# 02_MSP430.net
KiCad netlist of a schematic drawn in Altium Designer
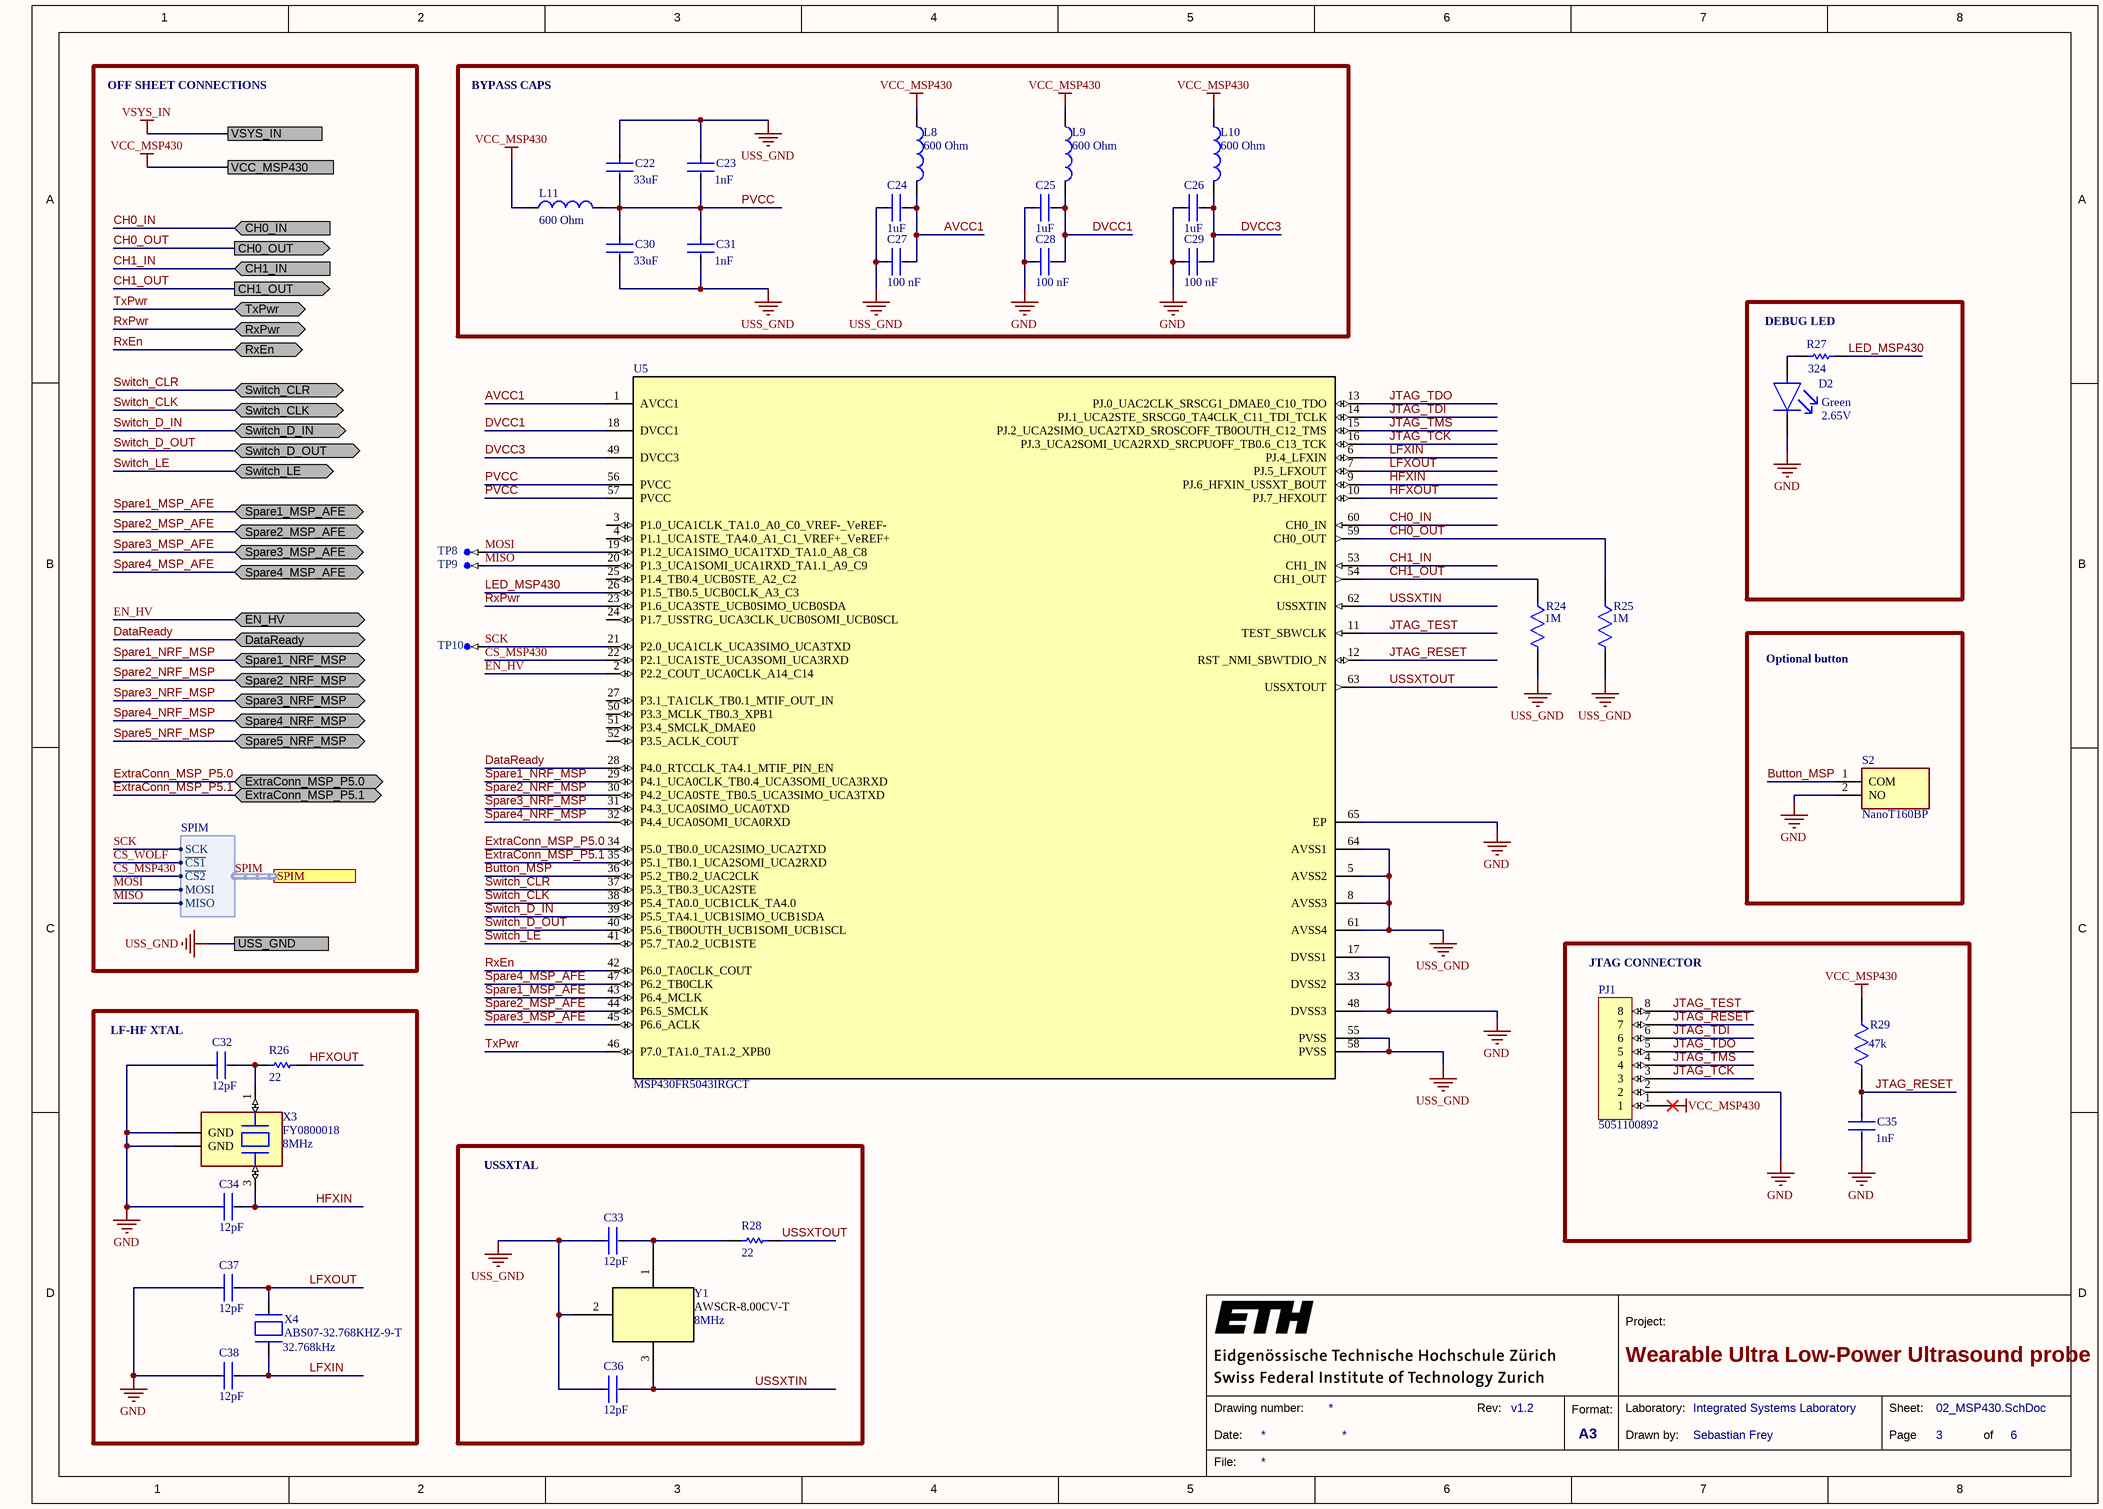
[diagram p0: 02_MSP430.SchDoc]

(export (version "E")
  (design (tool "Eeschema 10.0.6"))
  (components
    (comp (ref "C22")
      (value "C2012X5R1A336M125AC")
      (footprint "FP-C2012-125-0_2-IPC_A")
      (description "Multilayer Ceramic Capacitors 33μF ±20% 10V X5R SMD 0805")
      (fields (field (name "TOLERANCE") "20%") (field (name "CAPACITANCE") "33uF"))
      (libsource (lib "Altium Content Vault") (part "b4654b650e69147ec39a6b967a45e02"))
    )
    (comp (ref "C23")
      (value "GRM1555C1H102JA01D")
      (footprint "FP-GRM155-0_05-IPC_B")
      (description "Chip Multilayer Ceramic Capacitors for General Purpose, 0402, 1000pF, C0G, 30ppm/°C, 5%, 50V")
      (fields
        (field (name "TOLERANCE") "5%")
        (field (name "VOLTAGE") "50V")
        (field (name "CAPACITANCE") "1nF")
      )
      (libsource (lib "Altium Content Vault") (part "02cd4be3c70576c341d710602a673aa"))
    )
    (comp (ref "C24")
      (value "C1608X7R1C105K080AC")
      (footprint "FP-C1608-080-0_1-IPC_B")
      (description "Multilayer Ceramic Capacitors 1μF ±10% 16V X7R SMD 0603")
      (fields
        (field (name "VOLTAGE") "16V")
        (field (name "CAPACITANCE") "1uF")
        (field (name "TOLERANCE") "10%")
      )
      (libsource (lib "Altium Content Vault") (part "236180d848d6139a670b325ea6854c9"))
    )
    (comp (ref "C25")
      (value "C1608X7R1C105K080AC")
      (footprint "FP-C1608-080-0_1-IPC_B")
      (description "Multilayer Ceramic Capacitors 1μF ±10% 16V X7R SMD 0603")
      (fields
        (field (name "VOLTAGE") "16V")
        (field (name "CAPACITANCE") "1uF")
        (field (name "TOLERANCE") "10%")
      )
      (libsource (lib "Altium Content Vault") (part "236180d848d6139a670b325ea6854c9"))
    )
    (comp (ref "C26")
      (value "C1608X7R1C105K080AC")
      (footprint "FP-C1608-080-0_1-IPC_B")
      (description "Multilayer Ceramic Capacitors 1μF ±10% 16V X7R SMD 0603")
      (fields
        (field (name "VOLTAGE") "16V")
        (field (name "CAPACITANCE") "1uF")
        (field (name "TOLERANCE") "10%")
      )
      (libsource (lib "Altium Content Vault") (part "236180d848d6139a670b325ea6854c9"))
    )
    (comp (ref "C27")
      (value "100 nF")
      (footprint "FP-CC0402-MFG")
      (description "CAP CER 0.1UF 16V X7R 0402")
      (fields (field (name "MANUFACTURER") "YAGEO") (field (name "TOLERANCE") "0.1"))
      (libsource (lib "Altium Content Vault") (part "11868f565c42a9108669ba33697ecf6"))
    )
    (comp (ref "C28")
      (value "100 nF")
      (footprint "FP-CC0402-MFG")
      (description "CAP CER 0.1UF 16V X7R 0402")
      (fields (field (name "MANUFACTURER") "YAGEO") (field (name "TOLERANCE") "0.1"))
      (libsource (lib "Altium Content Vault") (part "11868f565c42a9108669ba33697ecf6"))
    )
    (comp (ref "C29")
      (value "100 nF")
      (footprint "FP-CC0402-MFG")
      (description "CAP CER 0.1UF 16V X7R 0402")
      (fields (field (name "MANUFACTURER") "YAGEO") (field (name "TOLERANCE") "0.1"))
      (libsource (lib "Altium Content Vault") (part "11868f565c42a9108669ba33697ecf6"))
    )
    (comp (ref "C30")
      (value "C2012X5R1A336M125AC")
      (footprint "FP-C2012-125-0_2-IPC_A")
      (description "Multilayer Ceramic Capacitors 33μF ±20% 10V X5R SMD 0805")
      (fields (field (name "TOLERANCE") "20%") (field (name "CAPACITANCE") "33uF"))
      (libsource (lib "Altium Content Vault") (part "b4654b650e69147ec39a6b967a45e02"))
    )
    (comp (ref "C31")
      (value "GRM1555C1H102JA01D")
      (footprint "FP-GRM155-0_05-IPC_B")
      (description "Chip Multilayer Ceramic Capacitors for General Purpose, 0402, 1000pF, C0G, 30ppm/°C, 5%, 50V")
      (fields
        (field (name "TOLERANCE") "5%")
        (field (name "VOLTAGE") "50V")
        (field (name "CAPACITANCE") "1nF")
      )
      (libsource (lib "Altium Content Vault") (part "02cd4be3c70576c341d710602a673aa"))
    )
    (comp (ref "C32")
      (value "GJM1555C1H120GB01D")
      (footprint "FP-GJM155-0_05-IPC_A")
      (description "Multi-Layer Ceramic Capacitor 12pF C0G  ±2% 0402 Paper T/R")
      (fields (field (name "TOLERANCE") "2%") (field (name "CAPACITANCE") "12pF"))
      (libsource (lib "Altium Content Vault") (part "02cd4be3c70576c341d710602a673aa"))
    )
    (comp (ref "C33")
      (value "GJM1555C1H120GB01D")
      (footprint "FP-GJM155-0_05-IPC_A")
      (description "Multi-Layer Ceramic Capacitor 12pF C0G  ±2% 0402 Paper T/R")
      (fields (field (name "TOLERANCE") "2%") (field (name "CAPACITANCE") "12pF"))
      (libsource (lib "Altium Content Vault") (part "02cd4be3c70576c341d710602a673aa"))
    )
    (comp (ref "C34")
      (value "GJM1555C1H120GB01D")
      (footprint "FP-GJM155-0_05-IPC_A")
      (description "Multi-Layer Ceramic Capacitor 12pF C0G  ±2% 0402 Paper T/R")
      (fields (field (name "TOLERANCE") "2%") (field (name "CAPACITANCE") "12pF"))
      (libsource (lib "Altium Content Vault") (part "02cd4be3c70576c341d710602a673aa"))
    )
    (comp (ref "C35")
      (value "GRM1555C1H102JA01D")
      (footprint "FP-GRM155-0_05-IPC_B")
      (description "Chip Multilayer Ceramic Capacitors for General Purpose, 0402, 1000pF, C0G, 30ppm/°C, 5%, 50V")
      (fields
        (field (name "TOLERANCE") "5%")
        (field (name "VOLTAGE") "50V")
        (field (name "CAPACITANCE") "1nF")
      )
      (libsource (lib "Altium Content Vault") (part "02cd4be3c70576c341d710602a673aa"))
    )
    (comp (ref "C36")
      (value "GJM1555C1H120GB01D")
      (footprint "FP-GJM155-0_05-IPC_A")
      (description "Multi-Layer Ceramic Capacitor 12pF C0G  ±2% 0402 Paper T/R")
      (fields (field (name "TOLERANCE") "2%") (field (name "CAPACITANCE") "12pF"))
      (libsource (lib "Altium Content Vault") (part "02cd4be3c70576c341d710602a673aa"))
    )
    (comp (ref "C37")
      (value "GJM1555C1H120GB01D")
      (footprint "FP-GJM155-0_05-IPC_A")
      (description "Multi-Layer Ceramic Capacitor 12pF C0G  ±2% 0402 Paper T/R")
      (fields (field (name "TOLERANCE") "2%") (field (name "CAPACITANCE") "12pF"))
      (libsource (lib "Altium Content Vault") (part "02cd4be3c70576c341d710602a673aa"))
    )
    (comp (ref "C38")
      (value "GJM1555C1H120GB01D")
      (footprint "FP-GJM155-0_05-IPC_A")
      (description "Multi-Layer Ceramic Capacitor 12pF C0G  ±2% 0402 Paper T/R")
      (fields (field (name "TOLERANCE") "2%") (field (name "CAPACITANCE") "12pF"))
      (libsource (lib "Altium Content Vault") (part "02cd4be3c70576c341d710602a673aa"))
    )
    (comp (ref "D2")
      (value "APHD1608LZGCK")
      (footprint "FP-APHD1608LZGCK-MFG")
      (description "LED GREEN CLEAR 1608 SMD")
      (fields (field (name "FORWARD VOLTAGE") "2.65V") (field (name "COLOR") "Green"))
      (libsource (lib "Altium Content Vault") (part "8706943c75ba83719d021d2fdc84c58"))
    )
    (comp (ref "L8")
      (value "742792040")
      (footprint "SMD-0805")
      (description "SMD EMI Suppression Ferrite Bead WE-CBF, Z = 600 Ohm")
      (fields (field (name "IMPEDANCE") "600 Ohm"))
      (libsource (lib "Altium Content Vault") (part "PAS-IND-INDUCTOR-2"))
    )
    (comp (ref "L9")
      (value "742792040")
      (footprint "SMD-0805")
      (description "SMD EMI Suppression Ferrite Bead WE-CBF, Z = 600 Ohm")
      (fields (field (name "IMPEDANCE") "600 Ohm"))
      (libsource (lib "Altium Content Vault") (part "PAS-IND-INDUCTOR-2"))
    )
    (comp (ref "L10")
      (value "742792040")
      (footprint "SMD-0805")
      (description "SMD EMI Suppression Ferrite Bead WE-CBF, Z = 600 Ohm")
      (fields (field (name "IMPEDANCE") "600 Ohm"))
      (libsource (lib "Altium Content Vault") (part "PAS-IND-INDUCTOR-2"))
    )
    (comp (ref "L11")
      (value "742792040")
      (footprint "SMD-0805")
      (description "SMD EMI Suppression Ferrite Bead WE-CBF, Z = 600 Ohm")
      (fields (field (name "IMPEDANCE") "600 Ohm"))
      (libsource (lib "Altium Content Vault") (part "PAS-IND-INDUCTOR-2"))
    )
    (comp (ref "PJ1")
      (value "5051100892")
      (footprint "PcbLib1:MOLEX_5051100892")
      (libsource (lib "Schlib1") (part "MOLEX_5051100892"))
    )
    (comp (ref "R24")
      (value "CRCW04021M00FKED")
      (footprint "FP-CRCW0402-e3-MFG")
      (description "RES Thick Film, 1MΩ, 1%, 0.063W, 100ppm/°C, 0402")
      (fields (field (name "TOLERANCE") "1%") (field (name "RESISTANCE") "1M"))
      (libsource (lib "Altium Content Vault") (part "1029c3af85768c4190bb7ad29bc67b5"))
    )
    (comp (ref "R25")
      (value "CRCW04021M00FKED")
      (footprint "FP-CRCW0402-e3-MFG")
      (description "RES Thick Film, 1MΩ, 1%, 0.063W, 100ppm/°C, 0402")
      (fields (field (name "TOLERANCE") "1%") (field (name "RESISTANCE") "1M"))
      (libsource (lib "Altium Content Vault") (part "1029c3af85768c4190bb7ad29bc67b5"))
    )
    (comp (ref "R26")
      (value "RC0402JR-0722RL")
      (footprint "RESC1005X40X25NL05T10")
      (fields (field (name "MANUFACTURER") "Yageo / Phycomp") (field (name "RESISTANCE") "22"))
      (libsource (lib "Altium Content Vault") (part "RES"))
    )
    (comp (ref "R27")
      (value "CPF0402B324RE1")
      (footprint "RESC1005X35X20ML05T10")
      (fields (field (name "MANUFACTURER") "TE Connectivity / AMP") (field (name "RESISTANCE") "324"))
      (libsource (lib "Altium Content Vault") (part "RES"))
    )
    (comp (ref "R28")
      (value "RC0402JR-0722RL")
      (footprint "RESC1005X40X25NL05T10")
      (fields (field (name "MANUFACTURER") "Yageo / Phycomp") (field (name "RESISTANCE") "22"))
      (libsource (lib "Altium Content Vault") (part "RES"))
    )
    (comp (ref "R29")
      (value "CRCW040247K0FKED")
      (footprint "FP-CRCW0402-e3-IPC_C")
      (description "RES Thick Film, 47kΩ, 1%, 0.063W, 100ppm/°C, 0402")
      (fields (field (name "TOLERANCE") "1%") (field (name "RESISTANCE") "47k"))
      (libsource (lib "Altium Content Vault") (part "1029c3af85768c4190bb7ad29bc67b5"))
    )
    (comp (ref "S2")
      (value "NanoT160BP")
      (footprint "PcbLib1:NanoT160BP")
      (description "Switch")
      (libsource (lib "Schlib1") (part "NanoT160BP"))
    )
    (comp (ref "TP8")
      (value "TP-SM-C-100")
      (footprint "TP-SM-C-100")
      (description "Test Point, Surface Mount, Circular, Pad Diameter 1 mm")
      (libsource (lib "Altium Content Vault") (part "TP-SM"))
    )
    (comp (ref "TP9")
      (value "TP-SM-C-100")
      (footprint "TP-SM-C-100")
      (description "Test Point, Surface Mount, Circular, Pad Diameter 1 mm")
      (libsource (lib "Altium Content Vault") (part "TP-SM"))
    )
    (comp (ref "TP10")
      (value "TP-SM-C-100")
      (footprint "TP-SM-C-100")
      (description "Test Point, Surface Mount, Circular, Pad Diameter 1 mm")
      (libsource (lib "Altium Content Vault") (part "TP-SM"))
    )
    (comp (ref "U5")
      (value "MSP430FR5043IRGCT")
      (footprint "PcbLib1:RGC0064G")
      (description "No Description Available")
      (fields (field (name "COPYRIGHT") "Copyright (C) 2021 Ultra Librarian. All rights reserved."))
      (libsource (lib "Schlib1") (part "MSP430FR5043IRGCT"))
    )
    (comp (ref "X3")
      (value "FY0800018")
      (footprint "PcbLib1:XTAL_ECS-80-18-30B-AGN-TR")
      (description "Crystal 8MHz ±30ppm (Tol) ±30ppm (Stability) 18pF FUND 100Ohm 4-Pin SMD T/R")
      (fields (field (name "MANUFACTURER") "Diodes") (field (name "FREQUENCY") "8MHz"))
      (libsource (lib "Schlib1") (part "FY0800018"))
    )
    (comp (ref "X4")
      (value "ABS07-32.768KHZ-9-T")
      (footprint "PcbLib1:XTAL320X150X90")
      (description "Crystal; Miniature; 3.2 x 1.5 x 0.9mm; 32.768KHZ; 9pf; 20ppm -40+85C; SMD; T/R")
      (fields
        (field (name "MANUFACTURER") "Abracon")
        (field (name "FREQUENCY") "32.768kHz")
        (field (name "TOLERANCE") "20ppm")
      )
      (libsource (lib "Schlib1") (part "ABS07-32.768KHZ-9-T"))
    )
    (comp (ref "Y1")
      (value "AWSCR-8.00CV-T")
      (footprint "PcbLib1:AWSCR-8.00CV-T_ABR")
      (description "No Description Available")
      (fields
        (field (name "MANUFACTURER_PART_NUMBER") "AWSCR-8.00CV-T")
        (field (name "FREQUENCY") "8MHz")
        (field (name "COPYRIGHT") "Copyright (C) 2021 Ultra Librarian. All rights reserved.")
      )
      (libsource (lib "Schlib1") (part "AWSCR-8.00CV-T"))
    )
  )
  (nets
    (net (code "2") (name "/AVCC1") (class "Default")
      (node (ref "C24") (pin "1") (pinfunction "1_1") (pintype "passive"))
      (node (ref "C27") (pin "2") (pinfunction "2_2") (pintype "passive"))
      (node (ref "L8") (pin "2") (pinfunction "2_2") (pintype "passive"))
      (node (ref "U5") (pin "1") (pinfunction "AVCC1_1") (pintype "power_in"))
    )
    (net (code "3") (name "/Button_MSP") (class "Default")
      (node (ref "S2") (pin "1") (pinfunction "COM_1") (pintype "passive"))
      (node (ref "U5") (pin "36") (pinfunction "P5.2_TB0.2_UAC2CLK_36") (pintype "bidirectional"))
    )
    (net (code "4") (name "/CH0_IN") (class "Default")
      (node (ref "U5") (pin "60") (pinfunction "CH0_IN_60") (pintype "input"))
    )
    (net (code "5") (name "/CH0_OUT") (class "Default")
      (node (ref "R25") (pin "1") (pinfunction "1_1") (pintype "passive"))
      (node (ref "U5") (pin "59") (pinfunction "CH0_OUT_59") (pintype "output"))
    )
    (net (code "6") (name "/CH1_IN") (class "Default")
      (node (ref "U5") (pin "53") (pinfunction "CH1_IN_53") (pintype "input"))
    )
    (net (code "7") (name "/CH1_OUT") (class "Default")
      (node (ref "R24") (pin "1") (pinfunction "1_1") (pintype "passive"))
      (node (ref "U5") (pin "54") (pinfunction "CH1_OUT_54") (pintype "output"))
    )
    (net (code "8") (name "/CS_MSP430") (class "Default")
      (node (ref "U5") (pin "22") (pinfunction "P2.1_UCA1STE_UCA3SOMI_UCA3RXD_22") (pintype "bidirectional"))
    )
    (net (code "10") (name "/DVCC1") (class "Default")
      (node (ref "C25") (pin "1") (pinfunction "1_1") (pintype "passive"))
      (node (ref "C28") (pin "2") (pinfunction "2_2") (pintype "passive"))
      (node (ref "L9") (pin "2") (pinfunction "2_2") (pintype "passive"))
      (node (ref "U5") (pin "18") (pinfunction "DVCC1_18") (pintype "power_in"))
    )
    (net (code "11") (name "/DVCC3") (class "Default")
      (node (ref "C26") (pin "1") (pinfunction "1_1") (pintype "passive"))
      (node (ref "C29") (pin "2") (pinfunction "2_2") (pintype "passive"))
      (node (ref "L10") (pin "2") (pinfunction "2_2") (pintype "passive"))
      (node (ref "U5") (pin "49") (pinfunction "DVCC3_49") (pintype "power_in"))
    )
    (net (code "12") (name "/DataReady") (class "Default")
      (node (ref "U5") (pin "28") (pinfunction "P4.0_RTCCLK_TA4.1_MTIF_PIN_EN_28") (pintype "bidirectional"))
    )
    (net (code "13") (name "/EN_HV") (class "Default")
      (node (ref "U5") (pin "2") (pinfunction "P2.2_COUT_UCA0CLK_A14_C14_2") (pintype "bidirectional"))
    )
    (net (code "14") (name "/ExtraConn_MSP_P5.0") (class "Default")
      (node (ref "U5") (pin "34") (pinfunction "P5.0_TB0.0_UCA2SIMO_UCA2TXD_34") (pintype "bidirectional"))
    )
    (net (code "15") (name "/ExtraConn_MSP_P5.1") (class "Default")
      (node (ref "U5") (pin "35") (pinfunction "P5.1_TB0.1_UCA2SOMI_UCA2RXD_35") (pintype "bidirectional"))
    )
    (net (code "16") (name "/HFXIN") (class "Default")
      (node (ref "C34") (pin "2") (pinfunction "2_2") (pintype "passive"))
      (node (ref "U5") (pin "9") (pinfunction "PJ.6_HFXIN_USSXT_BOUT_9") (pintype "bidirectional"))
      (node (ref "X3") (pin "3") (pinfunction "OUT/IN_3") (pintype "bidirectional"))
    )
    (net (code "17") (name "/HFXOUT") (class "Default")
      (node (ref "R26") (pin "2") (pinfunction "2_2") (pintype "passive"))
      (node (ref "U5") (pin "10") (pinfunction "PJ.7_HFXOUT_10") (pintype "bidirectional"))
    )
    (net (code "18") (name "/JTAG_RESET") (class "Default")
      (node (ref "C35") (pin "1") (pinfunction "1_1") (pintype "passive"))
      (node (ref "PJ1") (pin "7") (pinfunction "7_7") (pintype "bidirectional"))
      (node (ref "R29") (pin "2") (pinfunction "2_2") (pintype "passive"))
      (node (ref "U5") (pin "12") (pinfunction "RST__NMI_SBWTDIO_N_12") (pintype "bidirectional"))
    )
    (net (code "19") (name "/JTAG_TCK") (class "Default")
      (node (ref "PJ1") (pin "3") (pinfunction "3_3") (pintype "bidirectional"))
      (node (ref "U5") (pin "16") (pinfunction "PJ.3_UCA2SOMI_UCA2RXD_SRCPUOFF_TB0.6_C13_TCK_16") (pintype "bidirectional"))
    )
    (net (code "20") (name "/JTAG_TDI") (class "Default")
      (node (ref "PJ1") (pin "6") (pinfunction "6_6") (pintype "bidirectional"))
      (node (ref "U5") (pin "14") (pinfunction "PJ.1_UCA2STE_SRSCG0_TA4CLK_C11_TDI_TCLK_14") (pintype "bidirectional"))
    )
    (net (code "21") (name "/JTAG_TDO") (class "Default")
      (node (ref "PJ1") (pin "5") (pinfunction "5_5") (pintype "bidirectional"))
      (node (ref "U5") (pin "13") (pinfunction "PJ.0_UAC2CLK_SRSCG1_DMAE0_C10_TDO_13") (pintype "bidirectional"))
    )
    (net (code "22") (name "/JTAG_TEST") (class "Default")
      (node (ref "PJ1") (pin "8") (pinfunction "8_8") (pintype "bidirectional"))
      (node (ref "U5") (pin "11") (pinfunction "TEST_SBWCLK_11") (pintype "input"))
    )
    (net (code "23") (name "/JTAG_TMS") (class "Default")
      (node (ref "PJ1") (pin "4") (pinfunction "4_4") (pintype "bidirectional"))
      (node (ref "U5") (pin "15") (pinfunction "PJ.2_UCA2SIMO_UCA2TXD_SROSCOFF_TB0OUTH_C12_TMS_15") (pintype "bidirectional"))
    )
    (net (code "24") (name "/LED_MSP430") (class "Default")
      (node (ref "R27") (pin "1") (pinfunction "1_1") (pintype "passive"))
      (node (ref "U5") (pin "26") (pinfunction "P1.5_TB0.5_UCB0CLK_A3_C3_26") (pintype "bidirectional"))
    )
    (net (code "25") (name "/LFXIN") (class "Default")
      (node (ref "C38") (pin "2") (pinfunction "2_2") (pintype "passive"))
      (node (ref "U5") (pin "6") (pinfunction "PJ.4_LFXIN_6") (pintype "bidirectional"))
      (node (ref "X4") (pin "1") (pinfunction "1_1") (pintype "passive"))
    )
    (net (code "26") (name "/LFXOUT") (class "Default")
      (node (ref "C37") (pin "2") (pinfunction "2_2") (pintype "passive"))
      (node (ref "U5") (pin "7") (pinfunction "PJ.5_LFXOUT_7") (pintype "bidirectional"))
      (node (ref "X4") (pin "2") (pinfunction "2_2") (pintype "passive"))
    )
    (net (code "27") (name "/MISO") (class "Default")
      (node (ref "TP9") (pin "1") (pinfunction "1_1") (pintype "input"))
      (node (ref "U5") (pin "20") (pinfunction "P1.3_UCA1SOMI_UCA1RXD_TA1.1_A9_C9_20") (pintype "bidirectional"))
    )
    (net (code "28") (name "/MOSI") (class "Default")
      (node (ref "TP8") (pin "1") (pinfunction "1_1") (pintype "input"))
      (node (ref "U5") (pin "19") (pinfunction "P1.2_UCA1SIMO_UCA1TXD_TA1.0_A8_C8_19") (pintype "bidirectional"))
    )
    (net (code "29") (name "/PVCC") (class "Default")
      (node (ref "C22") (pin "2") (pinfunction "2_2") (pintype "passive"))
      (node (ref "C23") (pin "2") (pinfunction "2_2") (pintype "passive"))
      (node (ref "C30") (pin "1") (pinfunction "1_1") (pintype "passive"))
      (node (ref "C31") (pin "1") (pinfunction "1_1") (pintype "passive"))
      (node (ref "L11") (pin "2") (pinfunction "2_2") (pintype "passive"))
      (node (ref "U5") (pin "56") (pinfunction "PVCC_56") (pintype "power_in"))
      (node (ref "U5") (pin "57") (pinfunction "PVCC_57") (pintype "power_in"))
    )
    (net (code "30") (name "/RxEn") (class "Default")
      (node (ref "U5") (pin "42") (pinfunction "P6.0_TA0CLK_COUT_42") (pintype "bidirectional"))
    )
    (net (code "31") (name "/RxPwr") (class "Default")
      (node (ref "U5") (pin "23") (pinfunction "P1.6_UCA3STE_UCB0SIMO_UCB0SDA_23") (pintype "bidirectional"))
    )
    (net (code "32") (name "/SCK") (class "Default")
      (node (ref "TP10") (pin "1") (pinfunction "1_1") (pintype "input"))
      (node (ref "U5") (pin "21") (pinfunction "P2.0_UCA1CLK_UCA3SIMO_UCA3TXD_21") (pintype "bidirectional"))
    )
    (net (code "34") (name "/Spare1_MSP_AFE") (class "Default")
      (node (ref "U5") (pin "43") (pinfunction "P6.4_MCLK_43") (pintype "bidirectional"))
    )
    (net (code "35") (name "/Spare1_NRF_MSP") (class "Default")
      (node (ref "U5") (pin "29") (pinfunction "P4.1_UCA0CLK_TB0.4_UCA3SOMI_UCA3RXD_29") (pintype "bidirectional"))
    )
    (net (code "36") (name "/Spare2_MSP_AFE") (class "Default")
      (node (ref "U5") (pin "44") (pinfunction "P6.5_SMCLK_44") (pintype "bidirectional"))
    )
    (net (code "37") (name "/Spare2_NRF_MSP") (class "Default")
      (node (ref "U5") (pin "30") (pinfunction "P4.2_UCA0STE_TB0.5_UCA3SIMO_UCA3TXD_30") (pintype "bidirectional"))
    )
    (net (code "38") (name "/Spare3_MSP_AFE") (class "Default")
      (node (ref "U5") (pin "45") (pinfunction "P6.6_ACLK_45") (pintype "bidirectional"))
    )
    (net (code "39") (name "/Spare3_NRF_MSP") (class "Default")
      (node (ref "U5") (pin "31") (pinfunction "P4.3_UCA0SIMO_UCA0TXD_31") (pintype "bidirectional"))
    )
    (net (code "40") (name "/Spare4_MSP_AFE") (class "Default")
      (node (ref "U5") (pin "47") (pinfunction "P6.2_TB0CLK_47") (pintype "bidirectional"))
    )
    (net (code "41") (name "/Spare4_NRF_MSP") (class "Default")
      (node (ref "U5") (pin "32") (pinfunction "P4.4_UCA0SOMI_UCA0RXD_32") (pintype "bidirectional"))
    )
    (net (code "43") (name "/Switch_CLK") (class "Default")
      (node (ref "U5") (pin "38") (pinfunction "P5.4_TA0.0_UCB1CLK_TA4.0_38") (pintype "bidirectional"))
    )
    (net (code "44") (name "/Switch_CLR") (class "Default")
      (node (ref "U5") (pin "37") (pinfunction "P5.3_TB0.3_UCA2STE_37") (pintype "bidirectional"))
    )
    (net (code "45") (name "/Switch_D_IN") (class "Default")
      (node (ref "U5") (pin "39") (pinfunction "P5.5_TA4.1_UCB1SIMO_UCB1SDA_39") (pintype "bidirectional"))
    )
    (net (code "46") (name "/Switch_D_OUT") (class "Default")
      (node (ref "U5") (pin "40") (pinfunction "P5.6_TB0OUTH_UCB1SOMI_UCB1SCL_40") (pintype "bidirectional"))
    )
    (net (code "47") (name "/Switch_LE") (class "Default")
      (node (ref "U5") (pin "41") (pinfunction "P5.7_TA0.2_UCB1STE_41") (pintype "bidirectional"))
    )
    (net (code "48") (name "/TxPwr") (class "Default")
      (node (ref "U5") (pin "46") (pinfunction "P7.0_TA1.0_TA1.2_XPB0_46") (pintype "bidirectional"))
    )
    (net (code "49") (name "/USSXTIN") (class "Default")
      (node (ref "C36") (pin "2") (pinfunction "2_2") (pintype "passive"))
      (node (ref "U5") (pin "62") (pinfunction "USSXTIN_62") (pintype "input"))
      (node (ref "Y1") (pin "3") (pinfunction "3_3") (pintype "passive"))
    )
    (net (code "50") (name "/USSXTOUT") (class "Default")
      (node (ref "R28") (pin "2") (pinfunction "2_2") (pintype "passive"))
      (node (ref "U5") (pin "63") (pinfunction "USSXTOUT_63") (pintype "output"))
    )
    (net (code "51") (name "GND") (class "Default")
      (node (ref "C25") (pin "2") (pinfunction "2_2") (pintype "passive"))
      (node (ref "C26") (pin "2") (pinfunction "2_2") (pintype "passive"))
      (node (ref "C28") (pin "1") (pinfunction "1_1") (pintype "passive"))
      (node (ref "C29") (pin "1") (pinfunction "1_1") (pintype "passive"))
      (node (ref "C32") (pin "1") (pinfunction "1_1") (pintype "passive"))
      (node (ref "C34") (pin "1") (pinfunction "1_1") (pintype "passive"))
      (node (ref "C35") (pin "2") (pinfunction "2_2") (pintype "passive"))
      (node (ref "C37") (pin "1") (pinfunction "1_1") (pintype "passive"))
      (node (ref "C38") (pin "1") (pinfunction "1_1") (pintype "passive"))
      (node (ref "D2") (pin "1") (pinfunction "C_1") (pintype "passive"))
      (node (ref "PJ1") (pin "2") (pinfunction "2_2") (pintype "bidirectional"))
      (node (ref "S2") (pin "2") (pinfunction "NO_2") (pintype "passive"))
      (node (ref "U5") (pin "17") (pinfunction "DVSS1_17") (pintype "power_in"))
      (node (ref "U5") (pin "33") (pinfunction "DVSS2_33") (pintype "power_in"))
      (node (ref "U5") (pin "48") (pinfunction "DVSS3_48") (pintype "power_in"))
      (node (ref "U5") (pin "65") (pinfunction "EP_65") (pintype "passive"))
      (node (ref "X3") (pin "2") (pinfunction "GND_2") (pintype "power_in"))
      (node (ref "X3") (pin "4") (pinfunction "GND_4") (pintype "power_in"))
    )
    (net (code "52") (name "Net-(C33-Pad2)") (class "Default")
      (node (ref "C33") (pin "2") (pinfunction "2_2") (pintype "passive"))
      (node (ref "R28") (pin "1") (pinfunction "1_1") (pintype "passive"))
      (node (ref "Y1") (pin "1") (pinfunction "1_1") (pintype "passive"))
    )
    (net (code "53") (name "Net-(D2-A)") (class "Default")
      (node (ref "D2") (pin "2") (pinfunction "A_2") (pintype "passive"))
      (node (ref "R27") (pin "2") (pinfunction "2_2") (pintype "passive"))
    )
    (net (code "54") (name "Net-(X3-IN{slash}OUT)") (class "Default")
      (node (ref "C32") (pin "2") (pinfunction "2_2") (pintype "passive"))
      (node (ref "R26") (pin "1") (pinfunction "1_1") (pintype "passive"))
      (node (ref "X3") (pin "1") (pinfunction "IN/OUT_1") (pintype "bidirectional"))
    )
    (net (code "55") (name "USS_GND") (class "Default")
      (node (ref "C22") (pin "1") (pinfunction "1_1") (pintype "passive"))
      (node (ref "C23") (pin "1") (pinfunction "1_1") (pintype "passive"))
      (node (ref "C24") (pin "2") (pinfunction "2_2") (pintype "passive"))
      (node (ref "C27") (pin "1") (pinfunction "1_1") (pintype "passive"))
      (node (ref "C30") (pin "2") (pinfunction "2_2") (pintype "passive"))
      (node (ref "C31") (pin "2") (pinfunction "2_2") (pintype "passive"))
      (node (ref "C33") (pin "1") (pinfunction "1_1") (pintype "passive"))
      (node (ref "C36") (pin "1") (pinfunction "1_1") (pintype "passive"))
      (node (ref "R24") (pin "2") (pinfunction "2_2") (pintype "passive"))
      (node (ref "R25") (pin "2") (pinfunction "2_2") (pintype "passive"))
      (node (ref "U5") (pin "5") (pinfunction "AVSS2_5") (pintype "power_in"))
      (node (ref "U5") (pin "55") (pinfunction "PVSS_55") (pintype "power_in"))
      (node (ref "U5") (pin "58") (pinfunction "PVSS_58") (pintype "power_in"))
      (node (ref "U5") (pin "61") (pinfunction "AVSS4_61") (pintype "power_in"))
      (node (ref "U5") (pin "64") (pinfunction "AVSS1_64") (pintype "power_in"))
      (node (ref "U5") (pin "8") (pinfunction "AVSS3_8") (pintype "power_in"))
      (node (ref "Y1") (pin "2") (pinfunction "2_2") (pintype "passive"))
    )
    (net (code "56") (name "VCC_MSP430") (class "Default")
      (node (ref "L10") (pin "1") (pinfunction "1_1") (pintype "passive"))
      (node (ref "L11") (pin "1") (pinfunction "1_1") (pintype "passive"))
      (node (ref "L8") (pin "1") (pinfunction "1_1") (pintype "passive"))
      (node (ref "L9") (pin "1") (pinfunction "1_1") (pintype "passive"))
      (node (ref "PJ1") (pin "1") (pinfunction "1_1") (pintype "bidirectional"))
      (node (ref "R29") (pin "1") (pinfunction "1_1") (pintype "passive"))
    )
    (net (code "58") (name "unconnected-(U5-P1.0_UCA1CLK_TA1.0_A0_C0_VREF-_VeREF--Pad3)") (class "Default")
      (node (ref "U5") (pin "3") (pinfunction "P1.0_UCA1CLK_TA1.0_A0_C0_VREF-_VeREF-_3") (pintype "bidirectional"))
    )
    (net (code "59") (name "unconnected-(U5-P1.1_UCA1STE_TA4.0_A1_C1_VREF+_VeREF+-Pad4)") (class "Default")
      (node (ref "U5") (pin "4") (pinfunction "P1.1_UCA1STE_TA4.0_A1_C1_VREF+_VeREF+_4") (pintype "bidirectional"))
    )
    (net (code "60") (name "unconnected-(U5-P1.4_TB0.4_UCB0STE_A2_C2-Pad25)") (class "Default")
      (node (ref "U5") (pin "25") (pinfunction "P1.4_TB0.4_UCB0STE_A2_C2_25") (pintype "bidirectional"))
    )
    (net (code "61") (name "unconnected-(U5-P1.7_USSTRG_UCA3CLK_UCB0SOMI_UCB0SCL-Pad24)") (class "Default")
      (node (ref "U5") (pin "24") (pinfunction "P1.7_USSTRG_UCA3CLK_UCB0SOMI_UCB0SCL_24") (pintype "bidirectional"))
    )
    (net (code "62") (name "unconnected-(U5-P3.1_TA1CLK_TB0.1_MTIF_OUT_IN-Pad27)") (class "Default")
      (node (ref "U5") (pin "27") (pinfunction "P3.1_TA1CLK_TB0.1_MTIF_OUT_IN_27") (pintype "bidirectional"))
    )
    (net (code "63") (name "unconnected-(U5-P3.3_MCLK_TB0.3_XPB1-Pad50)") (class "Default")
      (node (ref "U5") (pin "50") (pinfunction "P3.3_MCLK_TB0.3_XPB1_50") (pintype "bidirectional"))
    )
    (net (code "64") (name "unconnected-(U5-P3.4_SMCLK_DMAE0-Pad51)") (class "Default")
      (node (ref "U5") (pin "51") (pinfunction "P3.4_SMCLK_DMAE0_51") (pintype "bidirectional"))
    )
    (net (code "65") (name "unconnected-(U5-P3.5_ACLK_COUT-Pad52)") (class "Default")
      (node (ref "U5") (pin "52") (pinfunction "P3.5_ACLK_COUT_52") (pintype "bidirectional"))
    )
  )
)
